# PWM_Chanels.net
KiCad netlist of a schematic drawn in Altium Designer
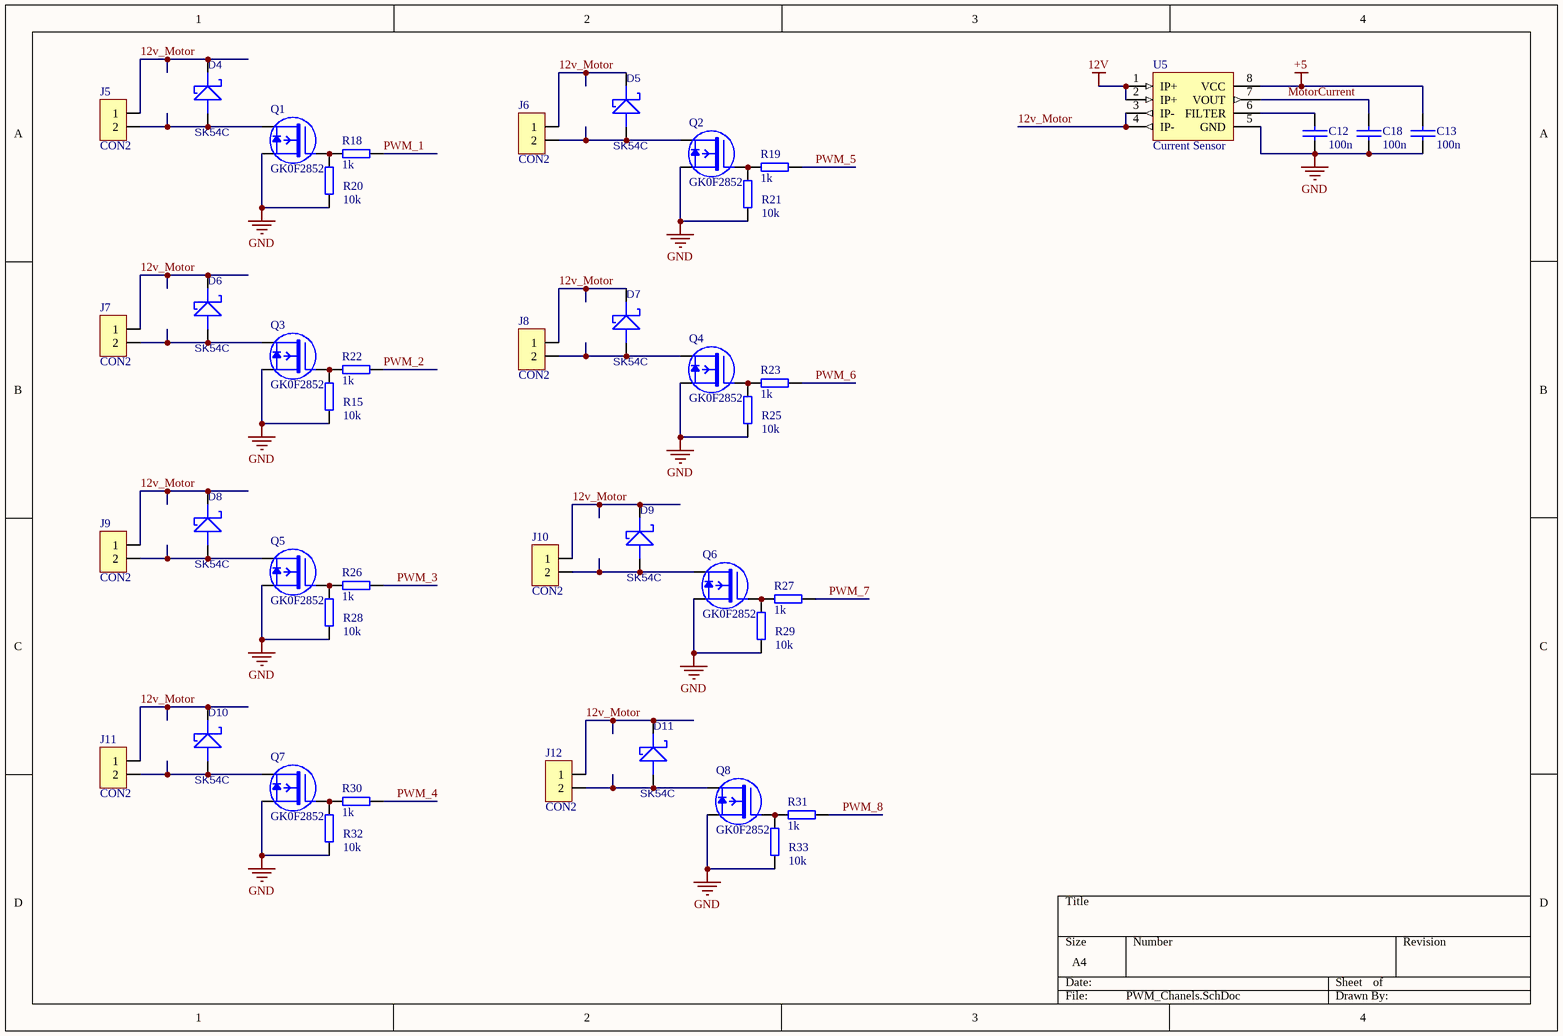
[diagram p0: PWM_Chanels.SchDoc]

(export (version "E")
  (design (tool "Eeschema 10.0.6"))
  (components
    (comp (ref "C12") (value "100n") (footprint "0603") (libsource (lib "DEVICE") (part "CAP")))
    (comp (ref "C13") (value "100n") (footprint "0603") (libsource (lib "DEVICE") (part "CAP")))
    (comp (ref "C18") (value "100n") (footprint "0603") (libsource (lib "DEVICE") (part "CAP")))
    (comp (ref "D4")
      (value "SK54C")
      (footprint "SMC")
      (fields (field (name "PARTNO") "1299291"))
      (libsource (lib "DEVICE") (part "DIODE SCHOTTKY"))
    )
    (comp (ref "D5")
      (value "SK54C")
      (footprint "SMC")
      (fields (field (name "PARTNO") "1299291"))
      (libsource (lib "DEVICE") (part "DIODE SCHOTTKY"))
    )
    (comp (ref "D6")
      (value "SK54C")
      (footprint "SMC")
      (fields (field (name "PARTNO") "1299291"))
      (libsource (lib "DEVICE") (part "DIODE SCHOTTKY"))
    )
    (comp (ref "D7")
      (value "SK54C")
      (footprint "SMC")
      (fields (field (name "PARTNO") "1299291"))
      (libsource (lib "DEVICE") (part "DIODE SCHOTTKY"))
    )
    (comp (ref "D8")
      (value "SK54C")
      (footprint "SMC")
      (fields (field (name "PARTNO") "1299291"))
      (libsource (lib "DEVICE") (part "DIODE SCHOTTKY"))
    )
    (comp (ref "D9")
      (value "SK54C")
      (footprint "SMC")
      (fields (field (name "PARTNO") "1299291"))
      (libsource (lib "DEVICE") (part "DIODE SCHOTTKY"))
    )
    (comp (ref "D10")
      (value "SK54C")
      (footprint "SMC")
      (fields (field (name "PARTNO") "1299291"))
      (libsource (lib "DEVICE") (part "DIODE SCHOTTKY"))
    )
    (comp (ref "D11")
      (value "SK54C")
      (footprint "SMC")
      (fields (field (name "PARTNO") "1299291"))
      (libsource (lib "DEVICE") (part "DIODE SCHOTTKY"))
    )
    (comp (ref "J5") (value "CON2") (footprint "WEID2R") (libsource (lib "DEVICE") (part "CON2")))
    (comp (ref "J6") (value "CON2") (footprint "WEID2R") (libsource (lib "DEVICE") (part "CON2")))
    (comp (ref "J7") (value "CON2") (footprint "WEID2R") (libsource (lib "DEVICE") (part "CON2")))
    (comp (ref "J8") (value "CON2") (footprint "WEID2R") (libsource (lib "DEVICE") (part "CON2")))
    (comp (ref "J9") (value "CON2") (footprint "WEID2R") (libsource (lib "DEVICE") (part "CON2")))
    (comp (ref "J10") (value "CON2") (footprint "WEID2R") (libsource (lib "DEVICE") (part "CON2")))
    (comp (ref "J11") (value "CON2") (footprint "WEID2R") (libsource (lib "DEVICE") (part "CON2")))
    (comp (ref "J12") (value "CON2") (footprint "WEID2R") (libsource (lib "DEVICE") (part "CON2")))
    (comp (ref "Q1")
      (value "GK0F2852")
      (footprint "TO-251")
      (libsource (lib "DEVICE") (part "MOSFET-N1DSML"))
    )
    (comp (ref "Q2")
      (value "GK0F2852")
      (footprint "TO-251")
      (libsource (lib "DEVICE") (part "MOSFET-N1DSML"))
    )
    (comp (ref "Q3")
      (value "GK0F2852")
      (footprint "TO-251")
      (libsource (lib "DEVICE") (part "MOSFET-N1DSML"))
    )
    (comp (ref "Q4")
      (value "GK0F2852")
      (footprint "TO-251")
      (libsource (lib "DEVICE") (part "MOSFET-N1DSML"))
    )
    (comp (ref "Q5")
      (value "GK0F2852")
      (footprint "TO-251")
      (libsource (lib "DEVICE") (part "MOSFET-N1DSML"))
    )
    (comp (ref "Q6")
      (value "GK0F2852")
      (footprint "TO-251")
      (libsource (lib "DEVICE") (part "MOSFET-N1DSML"))
    )
    (comp (ref "Q7")
      (value "GK0F2852")
      (footprint "TO-251")
      (libsource (lib "DEVICE") (part "MOSFET-N1DSML"))
    )
    (comp (ref "Q8")
      (value "GK0F2852")
      (footprint "TO-251")
      (libsource (lib "DEVICE") (part "MOSFET-N1DSML"))
    )
    (comp (ref "R15") (value "10k") (footprint "0603") (libsource (lib "DEVICE") (part "RES8")))
    (comp (ref "R18") (value "1k") (footprint "0603") (libsource (lib "DEVICE") (part "RES8")))
    (comp (ref "R19") (value "1k") (footprint "0603") (libsource (lib "DEVICE") (part "RES8")))
    (comp (ref "R20") (value "10k") (footprint "0603") (libsource (lib "DEVICE") (part "RES8")))
    (comp (ref "R21") (value "10k") (footprint "0603") (libsource (lib "DEVICE") (part "RES8")))
    (comp (ref "R22") (value "1k") (footprint "0603") (libsource (lib "DEVICE") (part "RES8")))
    (comp (ref "R23") (value "1k") (footprint "0603") (libsource (lib "DEVICE") (part "RES8")))
    (comp (ref "R25") (value "10k") (footprint "0603") (libsource (lib "DEVICE") (part "RES8")))
    (comp (ref "R26") (value "1k") (footprint "0603") (libsource (lib "DEVICE") (part "RES8")))
    (comp (ref "R27") (value "1k") (footprint "0603") (libsource (lib "DEVICE") (part "RES8")))
    (comp (ref "R28") (value "10k") (footprint "0603") (libsource (lib "DEVICE") (part "RES8")))
    (comp (ref "R29") (value "10k") (footprint "0603") (libsource (lib "DEVICE") (part "RES8")))
    (comp (ref "R30") (value "1k") (footprint "0603") (libsource (lib "DEVICE") (part "RES8")))
    (comp (ref "R31") (value "1k") (footprint "0603") (libsource (lib "DEVICE") (part "RES8")))
    (comp (ref "R32") (value "10k") (footprint "0603") (libsource (lib "DEVICE") (part "RES8")))
    (comp (ref "R33") (value "10k") (footprint "0603") (libsource (lib "DEVICE") (part "RES8")))
    (comp (ref "U5")
      (value "Current Sensor")
      (footprint "so-8")
      (description "+/- XA Current Sensor")
      (libsource (lib "TomsSchLib") (part "ACS714"))
    )
  )
  (nets
    (net (code "1") (name "+5") (class "Default")
      (node (ref "C13") (pin "2") (pintype "passive"))
      (node (ref "U5") (pin "8") (pinfunction "VCC_8") (pintype "power_in"))
    )
    (net (code "2") (name "/12v_Motor") (class "Default")
      (node (ref "D10") (pin "K") (pinfunction "K_K") (pintype "passive"))
      (node (ref "D11") (pin "K") (pinfunction "K_K") (pintype "passive"))
      (node (ref "D4") (pin "K") (pinfunction "K_K") (pintype "passive"))
      (node (ref "D5") (pin "K") (pinfunction "K_K") (pintype "passive"))
      (node (ref "D6") (pin "K") (pinfunction "K_K") (pintype "passive"))
      (node (ref "D7") (pin "K") (pinfunction "K_K") (pintype "passive"))
      (node (ref "D8") (pin "K") (pinfunction "K_K") (pintype "passive"))
      (node (ref "D9") (pin "K") (pinfunction "K_K") (pintype "passive"))
      (node (ref "J10") (pin "1") (pinfunction "1_1") (pintype "passive"))
      (node (ref "J11") (pin "1") (pinfunction "1_1") (pintype "passive"))
      (node (ref "J12") (pin "1") (pinfunction "1_1") (pintype "passive"))
      (node (ref "J5") (pin "1") (pinfunction "1_1") (pintype "passive"))
      (node (ref "J6") (pin "1") (pinfunction "1_1") (pintype "passive"))
      (node (ref "J7") (pin "1") (pinfunction "1_1") (pintype "passive"))
      (node (ref "J8") (pin "1") (pinfunction "1_1") (pintype "passive"))
      (node (ref "J9") (pin "1") (pinfunction "1_1") (pintype "passive"))
      (node (ref "U5") (pin "3") (pinfunction "IP-_3") (pintype "output"))
      (node (ref "U5") (pin "4") (pinfunction "IP-_4") (pintype "output"))
    )
    (net (code "3") (name "/MotorCurrent") (class "Default")
      (node (ref "C18") (pin "2") (pintype "passive"))
      (node (ref "U5") (pin "7") (pinfunction "VOUT_7") (pintype "output"))
    )
    (net (code "4") (name "/PWM_1") (class "Default") (node (ref "R18") (pin "1") (pintype "passive")))
    (net (code "5") (name "/PWM_2") (class "Default") (node (ref "R22") (pin "1") (pintype "passive")))
    (net (code "6") (name "/PWM_3") (class "Default") (node (ref "R26") (pin "1") (pintype "passive")))
    (net (code "7") (name "/PWM_4") (class "Default") (node (ref "R30") (pin "1") (pintype "passive")))
    (net (code "8") (name "/PWM_5") (class "Default") (node (ref "R19") (pin "1") (pintype "passive")))
    (net (code "9") (name "/PWM_6") (class "Default") (node (ref "R23") (pin "1") (pintype "passive")))
    (net (code "10") (name "/PWM_7") (class "Default") (node (ref "R27") (pin "1") (pintype "passive")))
    (net (code "11") (name "/PWM_8") (class "Default") (node (ref "R31") (pin "1") (pintype "passive")))
    (net (code "12") (name "12V") (class "Default")
      (node (ref "U5") (pin "1") (pinfunction "IP+_1") (pintype "input"))
      (node (ref "U5") (pin "2") (pinfunction "IP+_2") (pintype "input"))
    )
    (net (code "13") (name "GND") (class "Default")
      (node (ref "C12") (pin "1") (pintype "passive"))
      (node (ref "C13") (pin "1") (pintype "passive"))
      (node (ref "C18") (pin "1") (pintype "passive"))
      (node (ref "Q1") (pin "S") (pinfunction "S_S") (pintype "passive"))
      (node (ref "Q2") (pin "S") (pinfunction "S_S") (pintype "passive"))
      (node (ref "Q3") (pin "S") (pinfunction "S_S") (pintype "passive"))
      (node (ref "Q4") (pin "S") (pinfunction "S_S") (pintype "passive"))
      (node (ref "Q5") (pin "S") (pinfunction "S_S") (pintype "passive"))
      (node (ref "Q6") (pin "S") (pinfunction "S_S") (pintype "passive"))
      (node (ref "Q7") (pin "S") (pinfunction "S_S") (pintype "passive"))
      (node (ref "Q8") (pin "S") (pinfunction "S_S") (pintype "passive"))
      (node (ref "R15") (pin "2") (pintype "passive"))
      (node (ref "R20") (pin "2") (pintype "passive"))
      (node (ref "R21") (pin "2") (pintype "passive"))
      (node (ref "R25") (pin "2") (pintype "passive"))
      (node (ref "R28") (pin "2") (pintype "passive"))
      (node (ref "R29") (pin "2") (pintype "passive"))
      (node (ref "R32") (pin "2") (pintype "passive"))
      (node (ref "R33") (pin "2") (pintype "passive"))
      (node (ref "U5") (pin "5") (pinfunction "GND_5") (pintype "power_in"))
    )
    (net (code "14") (name "Net-(D4-PadA)") (class "Default")
      (node (ref "D4") (pin "A") (pinfunction "A_A") (pintype "passive"))
      (node (ref "J5") (pin "2") (pinfunction "2_2") (pintype "passive"))
      (node (ref "Q1") (pin "D") (pinfunction "D_D") (pintype "passive"))
    )
    (net (code "15") (name "Net-(D5-PadA)") (class "Default")
      (node (ref "D5") (pin "A") (pinfunction "A_A") (pintype "passive"))
      (node (ref "J6") (pin "2") (pinfunction "2_2") (pintype "passive"))
      (node (ref "Q2") (pin "D") (pinfunction "D_D") (pintype "passive"))
    )
    (net (code "16") (name "Net-(D6-PadA)") (class "Default")
      (node (ref "D6") (pin "A") (pinfunction "A_A") (pintype "passive"))
      (node (ref "J7") (pin "2") (pinfunction "2_2") (pintype "passive"))
      (node (ref "Q3") (pin "D") (pinfunction "D_D") (pintype "passive"))
    )
    (net (code "17") (name "Net-(D7-PadA)") (class "Default")
      (node (ref "D7") (pin "A") (pinfunction "A_A") (pintype "passive"))
      (node (ref "J8") (pin "2") (pinfunction "2_2") (pintype "passive"))
      (node (ref "Q4") (pin "D") (pinfunction "D_D") (pintype "passive"))
    )
    (net (code "18") (name "Net-(D8-PadA)") (class "Default")
      (node (ref "D8") (pin "A") (pinfunction "A_A") (pintype "passive"))
      (node (ref "J9") (pin "2") (pinfunction "2_2") (pintype "passive"))
      (node (ref "Q5") (pin "D") (pinfunction "D_D") (pintype "passive"))
    )
    (net (code "19") (name "Net-(D9-PadA)") (class "Default")
      (node (ref "D9") (pin "A") (pinfunction "A_A") (pintype "passive"))
      (node (ref "J10") (pin "2") (pinfunction "2_2") (pintype "passive"))
      (node (ref "Q6") (pin "D") (pinfunction "D_D") (pintype "passive"))
    )
    (net (code "20") (name "Net-(D10-PadA)") (class "Default")
      (node (ref "D10") (pin "A") (pinfunction "A_A") (pintype "passive"))
      (node (ref "J11") (pin "2") (pinfunction "2_2") (pintype "passive"))
      (node (ref "Q7") (pin "D") (pinfunction "D_D") (pintype "passive"))
    )
    (net (code "21") (name "Net-(D11-PadA)") (class "Default")
      (node (ref "D11") (pin "A") (pinfunction "A_A") (pintype "passive"))
      (node (ref "J12") (pin "2") (pinfunction "2_2") (pintype "passive"))
      (node (ref "Q8") (pin "D") (pinfunction "D_D") (pintype "passive"))
    )
    (net (code "22") (name "Net-(Q1-PadG)") (class "Default")
      (node (ref "Q1") (pin "G") (pinfunction "G_G") (pintype "passive"))
      (node (ref "R18") (pin "2") (pintype "passive"))
      (node (ref "R20") (pin "1") (pintype "passive"))
    )
    (net (code "23") (name "Net-(Q2-PadG)") (class "Default")
      (node (ref "Q2") (pin "G") (pinfunction "G_G") (pintype "passive"))
      (node (ref "R19") (pin "2") (pintype "passive"))
      (node (ref "R21") (pin "1") (pintype "passive"))
    )
    (net (code "24") (name "Net-(Q3-PadG)") (class "Default")
      (node (ref "Q3") (pin "G") (pinfunction "G_G") (pintype "passive"))
      (node (ref "R15") (pin "1") (pintype "passive"))
      (node (ref "R22") (pin "2") (pintype "passive"))
    )
    (net (code "25") (name "Net-(Q4-PadG)") (class "Default")
      (node (ref "Q4") (pin "G") (pinfunction "G_G") (pintype "passive"))
      (node (ref "R23") (pin "2") (pintype "passive"))
      (node (ref "R25") (pin "1") (pintype "passive"))
    )
    (net (code "26") (name "Net-(Q5-PadG)") (class "Default")
      (node (ref "Q5") (pin "G") (pinfunction "G_G") (pintype "passive"))
      (node (ref "R26") (pin "2") (pintype "passive"))
      (node (ref "R28") (pin "1") (pintype "passive"))
    )
    (net (code "27") (name "Net-(Q6-PadG)") (class "Default")
      (node (ref "Q6") (pin "G") (pinfunction "G_G") (pintype "passive"))
      (node (ref "R27") (pin "2") (pintype "passive"))
      (node (ref "R29") (pin "1") (pintype "passive"))
    )
    (net (code "28") (name "Net-(Q7-PadG)") (class "Default")
      (node (ref "Q7") (pin "G") (pinfunction "G_G") (pintype "passive"))
      (node (ref "R30") (pin "2") (pintype "passive"))
      (node (ref "R32") (pin "1") (pintype "passive"))
    )
    (net (code "29") (name "Net-(Q8-PadG)") (class "Default")
      (node (ref "Q8") (pin "G") (pinfunction "G_G") (pintype "passive"))
      (node (ref "R31") (pin "2") (pintype "passive"))
      (node (ref "R33") (pin "1") (pintype "passive"))
    )
    (net (code "30") (name "Net-(U5-FILTER)") (class "Default")
      (node (ref "C12") (pin "2") (pintype "passive"))
      (node (ref "U5") (pin "6") (pinfunction "FILTER_6") (pintype "passive"))
    )
  )
)
